# v1_4.net
KiCad netlist of a schematic drawn in EAGLE
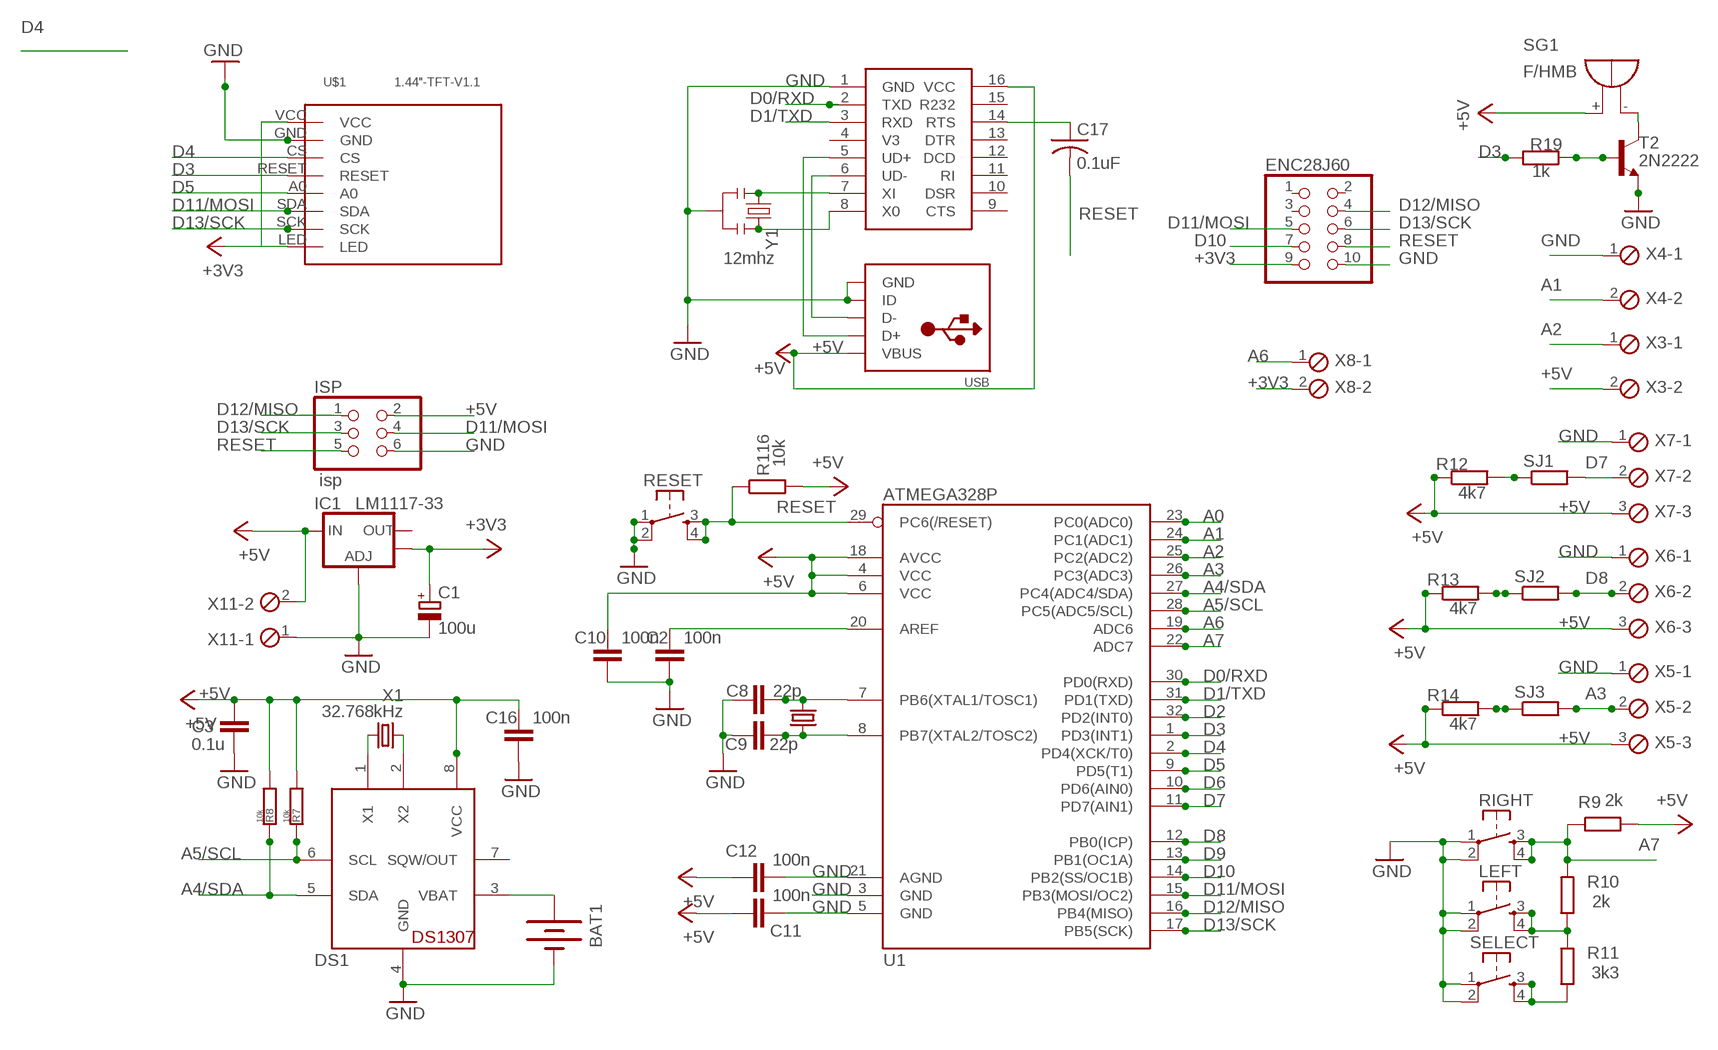
[diagram p0: schematic, sheet 1]

(export (version "E")
  (design (tool "Eeschema 10.0.6"))
  (components
    (comp (ref "BAT1")
      (value "BATTERY20PTH")
      (footprint "eagle-import:BATTCOM_20MM_PTH")
      (libsource (lib "eagle-import") (part "BATTERY20PTH"))
    )
    (comp (ref "C1")
      (value "100u")
      (footprint "eagle-import:E2-5")
      (libsource (lib "eagle-import") (part "CPOL-EUE2-5"))
    )
    (comp (ref "C2")
      (value "100n")
      (footprint "eagle-import:C0805")
      (libsource (lib "eagle-import") (part "resistor_C-EUC0805"))
    )
    (comp (ref "C3")
      (value "0.1u")
      (footprint "eagle-import:C0805")
      (libsource (lib "eagle-import") (part "C-EUC0805"))
    )
    (comp (ref "C8")
      (value "22p")
      (footprint "eagle-import:C0805")
      (libsource (lib "eagle-import") (part "resistor_C-EUC0805"))
    )
    (comp (ref "C9")
      (value "22p")
      (footprint "eagle-import:C0805")
      (libsource (lib "eagle-import") (part "resistor_C-EUC0805"))
    )
    (comp (ref "C10")
      (value "100n")
      (footprint "eagle-import:C0805")
      (libsource (lib "eagle-import") (part "resistor_C-EUC0805"))
    )
    (comp (ref "C11")
      (value "100n")
      (footprint "eagle-import:C0805")
      (libsource (lib "eagle-import") (part "resistor_C-EUC0805"))
    )
    (comp (ref "C12")
      (value "100n")
      (footprint "eagle-import:C0805")
      (libsource (lib "eagle-import") (part "resistor_C-EUC0805"))
    )
    (comp (ref "C16")
      (value "100n")
      (footprint "eagle-import:C0805")
      (libsource (lib "eagle-import") (part "resistor_C-EUC0805"))
    )
    (comp (ref "C17")
      (value "0.1uF")
      (footprint "eagle-import:C0805K")
      (libsource (lib "eagle-import") (part "C-USC0805K"))
    )
    (comp (ref "DS1")
      (value "DS1307")
      (footprint "eagle-import:SO08")
      (libsource (lib "eagle-import") (part "DS1307SOIC"))
    )
    (comp (ref "ENC28J60")
      (value "PINHD-2X5")
      (footprint "eagle-import:2X05")
      (libsource (lib "eagle-import") (part "PINHD-2X5"))
    )
    (comp (ref "IC1")
      (value "LM1117-33")
      (footprint "eagle-import:SOT223")
      (libsource (lib "eagle-import") (part "V_REG_LM1117SOT223"))
    )
    (comp (ref "ISP")
      (value "isp")
      (footprint "eagle-import:2X03")
      (libsource (lib "eagle-import") (part "PINHD-2X3"))
    )
    (comp (ref "LEFT")
      (value "TAC_SWITCHPTH")
      (footprint "eagle-import:TACTILE-PTH")
      (libsource (lib "eagle-import") (part "TAC_SWITCHPTH"))
    )
    (comp (ref "R7")
      (value "10k")
      (footprint "eagle-import:R0805")
      (libsource (lib "eagle-import") (part "R-EU_R0805"))
    )
    (comp (ref "R8")
      (value "10k")
      (footprint "eagle-import:R0805")
      (libsource (lib "eagle-import") (part "R-EU_R0805"))
    )
    (comp (ref "R9")
      (value "2k")
      (footprint "eagle-import:R0805")
      (libsource (lib "eagle-import") (part "R-EU_R0805"))
    )
    (comp (ref "R10")
      (value "2k")
      (footprint "eagle-import:R0805")
      (libsource (lib "eagle-import") (part "R-EU_R0805"))
    )
    (comp (ref "R11")
      (value "3k3")
      (footprint "eagle-import:R0805")
      (libsource (lib "eagle-import") (part "R-EU_R0805"))
    )
    (comp (ref "R12")
      (value "4k7")
      (footprint "eagle-import:R0805")
      (libsource (lib "eagle-import") (part "R-EU_R0805"))
    )
    (comp (ref "R13")
      (value "4k7")
      (footprint "eagle-import:R0805")
      (libsource (lib "eagle-import") (part "R-EU_R0805"))
    )
    (comp (ref "R14")
      (value "4k7")
      (footprint "eagle-import:R0805")
      (libsource (lib "eagle-import") (part "R-EU_R0805"))
    )
    (comp (ref "R19")
      (value "1k")
      (footprint "eagle-import:R0805")
      (libsource (lib "eagle-import") (part "R-EU_R0805"))
    )
    (comp (ref "R116")
      (value "10k")
      (footprint "eagle-import:R0805")
      (libsource (lib "eagle-import") (part "R-EU_R0805"))
    )
    (comp (ref "RESET")
      (value "TAC_SWITCHPTH")
      (footprint "eagle-import:TACTILE-PTH")
      (libsource (lib "eagle-import") (part "TAC_SWITCHPTH"))
    )
    (comp (ref "RIGHT")
      (value "TAC_SWITCHPTH")
      (footprint "eagle-import:TACTILE-PTH")
      (libsource (lib "eagle-import") (part "TAC_SWITCHPTH"))
    )
    (comp (ref "SELECT")
      (value "TAC_SWITCHPTH")
      (footprint "eagle-import:TACTILE-PTH")
      (libsource (lib "eagle-import") (part "TAC_SWITCHPTH"))
    )
    (comp (ref "SG1")
      (value "F/HMB")
      (footprint "eagle-import:F_HMB")
      (libsource (lib "eagle-import") (part "F/HMB"))
    )
    (comp (ref "SJ1")
      (value "R-EU_R0402")
      (footprint "eagle-import:R0402")
      (libsource (lib "eagle-import") (part "R-EU_R0402"))
    )
    (comp (ref "SJ2")
      (value "R-EU_R0402")
      (footprint "eagle-import:R0402")
      (libsource (lib "eagle-import") (part "R-EU_R0402"))
    )
    (comp (ref "SJ3")
      (value "R-EU_R0402")
      (footprint "eagle-import:R0402")
      (libsource (lib "eagle-import") (part "R-EU_R0402"))
    )
    (comp (ref "T2")
      (value "2N2222")
      (footprint "eagle-import:TO92-EBC-OVAL")
      (libsource (lib "eagle-import") (part "2N2222"))
    )
    (comp (ref "U$1")
      (value "1.44\"-TFT-V1.1")
      (footprint "eagle-import:1.44-TFT-V1.1")
      (libsource (lib "eagle-import") (part "1.44{dblquote}-TFT-V1.1"))
    )
    (comp (ref "U$2")
      (value "CH340G")
      (footprint "eagle-import:SO016")
      (libsource (lib "eagle-import") (part "CH340G"))
    )
    (comp (ref "U1")
      (value "ATMEGA328P")
      (footprint "eagle-import:TQFP32-08")
      (libsource (lib "eagle-import") (part "ATMEGA328_SMT"))
    )
    (comp (ref "USB")
      (value "USBMOLEX")
      (footprint "eagle-import:USB-MINIB-THM-MOLEX")
      (libsource (lib "eagle-import") (part "USBMOLEX"))
    )
    (comp (ref "X1")
      (value "32.768kHz")
      (footprint "eagle-import:TC26H")
      (libsource (lib "eagle-import") (part "crystal_CRYSTALTC26H"))
    )
    (comp (ref "X2")
      (value "16MHz")
      (footprint "eagle-import:HC49US")
      (libsource (lib "eagle-import") (part "CRYSTALHC49US"))
    )
    (comp (ref "X3")
      (value "MPT2")
      (footprint "eagle-import:2POL254")
      (libsource (lib "eagle-import") (part "MPT2"))
    )
    (comp (ref "X4")
      (value "MPT2")
      (footprint "eagle-import:2POL254")
      (libsource (lib "eagle-import") (part "MPT2"))
    )
    (comp (ref "X5")
      (value "MPT3")
      (footprint "eagle-import:3POL254")
      (libsource (lib "eagle-import") (part "MPT3"))
    )
    (comp (ref "X6")
      (value "MPT3")
      (footprint "eagle-import:3POL254")
      (libsource (lib "eagle-import") (part "MPT3"))
    )
    (comp (ref "X7")
      (value "MPT3")
      (footprint "eagle-import:3POL254")
      (libsource (lib "eagle-import") (part "MPT3"))
    )
    (comp (ref "X8")
      (value "MPT2")
      (footprint "eagle-import:2POL254")
      (libsource (lib "eagle-import") (part "MPT2"))
    )
    (comp (ref "X11")
      (value "MPT2")
      (footprint "eagle-import:2POL254")
      (fields (field (name "OC_FARNELL") "unknown") (field (name "OC_NEWARK") "unknown"))
      (libsource (lib "eagle-import") (part "MPT2"))
    )
    (comp (ref "Y1")
      (value "12mhz")
      (footprint "eagle-import:RESONATOR-PTH")
      (libsource (lib "eagle-import") (part "RESONATORPTH"))
    )
  )
  (nets
    (net (code "1") (name "+3V3") (class "Default")
      (node (ref "C1") (pin "+") (pinfunction "+_+") (pintype "passive"))
      (node (ref "ENC28J60") (pin "9") (pinfunction "9_9") (pintype "passive"))
      (node (ref "IC1") (pin "4") (pinfunction "OUT_4") (pintype "bidirectional"))
      (node (ref "U$1") (pin "LED") (pinfunction "LED_LED") (pintype "bidirectional"))
      (node (ref "U$1") (pin "VCC") (pinfunction "VCC_VCC") (pintype "bidirectional"))
      (node (ref "X8") (pin "2") (pinfunction "1_2") (pintype "passive"))
    )
    (net (code "2") (name "+5V") (class "Default")
      (node (ref "C10") (pin "1") (pinfunction "1_1") (pintype "passive"))
      (node (ref "C11") (pin "2") (pinfunction "2_2") (pintype "passive"))
      (node (ref "C12") (pin "2") (pinfunction "2_2") (pintype "passive"))
      (node (ref "C16") (pin "1") (pinfunction "1_1") (pintype "passive"))
      (node (ref "C3") (pin "1") (pinfunction "1_1") (pintype "passive"))
      (node (ref "DS1") (pin "8") (pinfunction "VCC_8") (pintype "power_in"))
      (node (ref "IC1") (pin "3") (pinfunction "IN_3") (pintype "input"))
      (node (ref "ISP") (pin "2") (pinfunction "2_2") (pintype "passive"))
      (node (ref "R116") (pin "2") (pinfunction "2_2") (pintype "passive"))
      (node (ref "R12") (pin "1") (pinfunction "1_1") (pintype "passive"))
      (node (ref "R13") (pin "1") (pinfunction "1_1") (pintype "passive"))
      (node (ref "R14") (pin "1") (pinfunction "1_1") (pintype "passive"))
      (node (ref "R7") (pin "2") (pinfunction "2_2") (pintype "passive"))
      (node (ref "R8") (pin "2") (pinfunction "2_2") (pintype "passive"))
      (node (ref "R9") (pin "2") (pinfunction "2_2") (pintype "passive"))
      (node (ref "SG1") (pin "+") (pinfunction "+_+") (pintype "passive"))
      (node (ref "U$2") (pin "16") (pinfunction "VCC_16") (pintype "bidirectional"))
      (node (ref "U1") (pin "18") (pinfunction "AVCC_18") (pintype "bidirectional"))
      (node (ref "U1") (pin "4") (pinfunction "VCC_4") (pintype "bidirectional"))
      (node (ref "U1") (pin "6") (pinfunction "VCC_6") (pintype "bidirectional"))
      (node (ref "USB") (pin "VBUS") (pinfunction "VBUS_VBUS") (pintype "power_in"))
      (node (ref "X11") (pin "2") (pinfunction "1_2") (pintype "passive"))
      (node (ref "X3") (pin "2") (pinfunction "1_2") (pintype "passive"))
      (node (ref "X5") (pin "3") (pinfunction "1_3") (pintype "passive"))
      (node (ref "X6") (pin "3") (pinfunction "1_3") (pintype "passive"))
      (node (ref "X7") (pin "3") (pinfunction "1_3") (pintype "passive"))
    )
    (net (code "3") (name "/A0") (class "Default")
      (node (ref "U1") (pin "23") (pinfunction "PC0(ADC0)_23") (pintype "bidirectional"))
    )
    (net (code "4") (name "/A1") (class "Default")
      (node (ref "U1") (pin "24") (pinfunction "PC1(ADC1)_24") (pintype "bidirectional"))
      (node (ref "X4") (pin "2") (pinfunction "1_2") (pintype "passive"))
    )
    (net (code "5") (name "/A2") (class "Default")
      (node (ref "U1") (pin "25") (pinfunction "PC2(ADC2)_25") (pintype "bidirectional"))
      (node (ref "X3") (pin "1") (pinfunction "1_1") (pintype "passive"))
    )
    (net (code "6") (name "/A3") (class "Default")
      (node (ref "SJ3") (pin "2") (pinfunction "2_2") (pintype "passive"))
      (node (ref "U1") (pin "26") (pinfunction "PC3(ADC3)_26") (pintype "bidirectional"))
      (node (ref "X5") (pin "2") (pinfunction "1_2") (pintype "passive"))
    )
    (net (code "7") (name "/A4{slash}SDA") (class "Default")
      (node (ref "DS1") (pin "5") (pinfunction "SDA_5") (pintype "bidirectional"))
      (node (ref "R8") (pin "1") (pinfunction "1_1") (pintype "passive"))
      (node (ref "U1") (pin "27") (pinfunction "PC4(ADC4/SDA)_27") (pintype "bidirectional"))
    )
    (net (code "8") (name "/A5{slash}SCL") (class "Default")
      (node (ref "DS1") (pin "6") (pinfunction "SCL_6") (pintype "bidirectional"))
      (node (ref "R7") (pin "1") (pinfunction "1_1") (pintype "passive"))
      (node (ref "U1") (pin "28") (pinfunction "PC5(ADC5/SCL)_28") (pintype "bidirectional"))
    )
    (net (code "9") (name "/A6") (class "Default")
      (node (ref "U1") (pin "19") (pinfunction "ADC6_19") (pintype "bidirectional"))
      (node (ref "X8") (pin "1") (pinfunction "1_1") (pintype "passive"))
    )
    (net (code "10") (name "/A7") (class "Default")
      (node (ref "R10") (pin "2") (pinfunction "2_2") (pintype "passive"))
      (node (ref "R9") (pin "1") (pinfunction "1_1") (pintype "passive"))
      (node (ref "RIGHT") (pin "3") (pinfunction "3_3") (pintype "passive"))
      (node (ref "RIGHT") (pin "4") (pinfunction "4_4") (pintype "passive"))
      (node (ref "U1") (pin "22") (pinfunction "ADC7_22") (pintype "bidirectional"))
    )
    (net (code "11") (name "/D0{slash}RXD") (class "Default")
      (node (ref "U$2") (pin "2") (pinfunction "TXD_2") (pintype "bidirectional"))
      (node (ref "U1") (pin "30") (pinfunction "PD0(RXD)_30") (pintype "bidirectional"))
    )
    (net (code "12") (name "/D1{slash}TXD") (class "Default")
      (node (ref "U$2") (pin "3") (pinfunction "RXD_3") (pintype "bidirectional"))
      (node (ref "U1") (pin "31") (pinfunction "PD1(TXD)_31") (pintype "bidirectional"))
    )
    (net (code "13") (name "/D2") (class "Default")
      (node (ref "U1") (pin "32") (pinfunction "PD2(INT0)_32") (pintype "bidirectional"))
    )
    (net (code "14") (name "/D3") (class "Default")
      (node (ref "R19") (pin "2") (pinfunction "2_2") (pintype "passive"))
      (node (ref "U$1") (pin "RESET") (pinfunction "RESET_RESET") (pintype "bidirectional"))
      (node (ref "U1") (pin "1") (pinfunction "PD3(INT1)_1") (pintype "bidirectional"))
    )
    (net (code "15") (name "/D4") (class "Default")
      (node (ref "U$1") (pin "CS") (pinfunction "CS_CS") (pintype "bidirectional"))
      (node (ref "U1") (pin "2") (pinfunction "PD4(XCK/T0)_2") (pintype "bidirectional"))
    )
    (net (code "16") (name "/D5") (class "Default")
      (node (ref "U$1") (pin "A0") (pinfunction "A0_A0") (pintype "bidirectional"))
      (node (ref "U1") (pin "9") (pinfunction "PD5(T1)_9") (pintype "bidirectional"))
    )
    (net (code "17") (name "/D6") (class "Default")
      (node (ref "U1") (pin "10") (pinfunction "PD6(AIN0)_10") (pintype "bidirectional"))
    )
    (net (code "18") (name "/D7") (class "Default")
      (node (ref "SJ1") (pin "2") (pinfunction "2_2") (pintype "passive"))
      (node (ref "U1") (pin "11") (pinfunction "PD7(AIN1)_11") (pintype "bidirectional"))
      (node (ref "X7") (pin "2") (pinfunction "1_2") (pintype "passive"))
    )
    (net (code "19") (name "/D8") (class "Default")
      (node (ref "SJ2") (pin "2") (pinfunction "2_2") (pintype "passive"))
      (node (ref "U1") (pin "12") (pinfunction "PB0(ICP)_12") (pintype "bidirectional"))
      (node (ref "X6") (pin "2") (pinfunction "1_2") (pintype "passive"))
    )
    (net (code "20") (name "/D9") (class "Default")
      (node (ref "U1") (pin "13") (pinfunction "PB1(OC1A)_13") (pintype "bidirectional"))
    )
    (net (code "21") (name "/D10") (class "Default")
      (node (ref "ENC28J60") (pin "7") (pinfunction "7_7") (pintype "passive"))
      (node (ref "U1") (pin "14") (pinfunction "PB2(SS/OC1B)_14") (pintype "bidirectional"))
    )
    (net (code "22") (name "/D11{slash}MOSI") (class "Default")
      (node (ref "ENC28J60") (pin "5") (pinfunction "5_5") (pintype "passive"))
      (node (ref "ISP") (pin "4") (pinfunction "4_4") (pintype "passive"))
      (node (ref "U$1") (pin "SDA") (pinfunction "SDA_SDA") (pintype "bidirectional"))
      (node (ref "U1") (pin "15") (pinfunction "PB3(MOSI/OC2)_15") (pintype "bidirectional"))
    )
    (net (code "23") (name "/D12{slash}MISO") (class "Default")
      (node (ref "ENC28J60") (pin "4") (pinfunction "4_4") (pintype "passive"))
      (node (ref "ISP") (pin "1") (pinfunction "1_1") (pintype "passive"))
      (node (ref "U1") (pin "16") (pinfunction "PB4(MISO)_16") (pintype "bidirectional"))
    )
    (net (code "24") (name "/D13{slash}SCK") (class "Default")
      (node (ref "ENC28J60") (pin "6") (pinfunction "6_6") (pintype "passive"))
      (node (ref "ISP") (pin "3") (pinfunction "3_3") (pintype "passive"))
      (node (ref "U$1") (pin "SCK") (pinfunction "SCK_SCK") (pintype "bidirectional"))
      (node (ref "U1") (pin "17") (pinfunction "PB5(SCK)_17") (pintype "bidirectional"))
    )
    (net (code "25") (name "/RESET") (class "Default")
      (node (ref "C17") (pin "2") (pinfunction "2_2") (pintype "passive"))
      (node (ref "ENC28J60") (pin "8") (pinfunction "8_8") (pintype "passive"))
      (node (ref "ISP") (pin "5") (pinfunction "5_5") (pintype "passive"))
      (node (ref "R116") (pin "1") (pinfunction "1_1") (pintype "passive"))
      (node (ref "RESET") (pin "3") (pinfunction "3_3") (pintype "passive"))
      (node (ref "RESET") (pin "4") (pinfunction "4_4") (pintype "passive"))
      (node (ref "U1") (pin "29") (pinfunction "PC6(/RESET)_29") (pintype "bidirectional"))
    )
    (net (code "26") (name "GND") (class "Default")
      (node (ref "BAT1") (pin "2") (pinfunction "-_2") (pintype "power_in"))
      (node (ref "C1") (pin "-") (pinfunction "-_-") (pintype "passive"))
      (node (ref "C10") (pin "2") (pinfunction "2_2") (pintype "passive"))
      (node (ref "C11") (pin "1") (pinfunction "1_1") (pintype "passive"))
      (node (ref "C12") (pin "1") (pinfunction "1_1") (pintype "passive"))
      (node (ref "C16") (pin "2") (pinfunction "2_2") (pintype "passive"))
      (node (ref "C2") (pin "2") (pinfunction "2_2") (pintype "passive"))
      (node (ref "C3") (pin "2") (pinfunction "2_2") (pintype "passive"))
      (node (ref "C8") (pin "1") (pinfunction "1_1") (pintype "passive"))
      (node (ref "C9") (pin "1") (pinfunction "1_1") (pintype "passive"))
      (node (ref "DS1") (pin "4") (pinfunction "GND_4") (pintype "power_in"))
      (node (ref "ENC28J60") (pin "10") (pinfunction "10_10") (pintype "passive"))
      (node (ref "IC1") (pin "1") (pinfunction "ADJ_1") (pintype "input"))
      (node (ref "ISP") (pin "6") (pinfunction "6_6") (pintype "passive"))
      (node (ref "LEFT") (pin "1") (pinfunction "1_1") (pintype "passive"))
      (node (ref "LEFT") (pin "2") (pinfunction "2_2") (pintype "passive"))
      (node (ref "RESET") (pin "1") (pinfunction "1_1") (pintype "passive"))
      (node (ref "RESET") (pin "2") (pinfunction "2_2") (pintype "passive"))
      (node (ref "RIGHT") (pin "1") (pinfunction "1_1") (pintype "passive"))
      (node (ref "RIGHT") (pin "2") (pinfunction "2_2") (pintype "passive"))
      (node (ref "SELECT") (pin "1") (pinfunction "1_1") (pintype "passive"))
      (node (ref "SELECT") (pin "2") (pinfunction "2_2") (pintype "passive"))
      (node (ref "T2") (pin "E") (pinfunction "E_E") (pintype "passive"))
      (node (ref "U$1") (pin "GND") (pinfunction "GND_GND") (pintype "bidirectional"))
      (node (ref "U$2") (pin "1") (pinfunction "GND_1") (pintype "bidirectional"))
      (node (ref "U1") (pin "21") (pinfunction "AGND_21") (pintype "bidirectional"))
      (node (ref "U1") (pin "3") (pinfunction "GND_3") (pintype "bidirectional"))
      (node (ref "U1") (pin "5") (pinfunction "GND_5") (pintype "bidirectional"))
      (node (ref "USB") (pin "GND") (pinfunction "GND_GND") (pintype "power_in"))
      (node (ref "USB") (pin "ID") (pinfunction "ID_ID") (pintype "bidirectional"))
      (node (ref "X11") (pin "1") (pinfunction "1_1") (pintype "passive"))
      (node (ref "X4") (pin "1") (pinfunction "1_1") (pintype "passive"))
      (node (ref "X5") (pin "1") (pinfunction "1_1") (pintype "passive"))
      (node (ref "X6") (pin "1") (pinfunction "1_1") (pintype "passive"))
      (node (ref "X7") (pin "1") (pinfunction "1_1") (pintype "passive"))
      (node (ref "Y1") (pin "2") (pinfunction "2_2") (pintype "passive"))
    )
    (net (code "27") (name "Net-(BAT1-+)") (class "Default")
      (node (ref "BAT1") (pin "1") (pinfunction "+_1") (pintype "power_in"))
      (node (ref "DS1") (pin "3") (pinfunction "VBAT_3") (pintype "power_in"))
    )
    (net (code "28") (name "Net-(DS1-X1)") (class "Default")
      (node (ref "DS1") (pin "1") (pinfunction "X1_1") (pintype "passive"))
      (node (ref "X1") (pin "2") (pinfunction "2_2") (pintype "passive"))
    )
    (net (code "29") (name "Net-(DS1-X2)") (class "Default")
      (node (ref "DS1") (pin "2") (pinfunction "X2_2") (pintype "passive"))
      (node (ref "X1") (pin "1") (pinfunction "1_1") (pintype "passive"))
    )
    (net (code "30") (name "Net-(LEFT-Pad3)") (class "Default")
      (node (ref "LEFT") (pin "3") (pinfunction "3_3") (pintype "passive"))
      (node (ref "LEFT") (pin "4") (pinfunction "4_4") (pintype "passive"))
      (node (ref "R10") (pin "1") (pinfunction "1_1") (pintype "passive"))
      (node (ref "R11") (pin "2") (pinfunction "2_2") (pintype "passive"))
    )
    (net (code "31") (name "Net-(R11-Pad1)") (class "Default")
      (node (ref "R11") (pin "1") (pinfunction "1_1") (pintype "passive"))
      (node (ref "SELECT") (pin "3") (pinfunction "3_3") (pintype "passive"))
      (node (ref "SELECT") (pin "4") (pinfunction "4_4") (pintype "passive"))
    )
    (net (code "32") (name "Net-(R12-Pad2)") (class "Default")
      (node (ref "R12") (pin "2") (pinfunction "2_2") (pintype "passive"))
      (node (ref "SJ1") (pin "1") (pinfunction "1_1") (pintype "passive"))
    )
    (net (code "33") (name "Net-(R13-Pad2)") (class "Default")
      (node (ref "R13") (pin "2") (pinfunction "2_2") (pintype "passive"))
      (node (ref "SJ2") (pin "1") (pinfunction "1_1") (pintype "passive"))
    )
    (net (code "34") (name "Net-(R14-Pad2)") (class "Default")
      (node (ref "R14") (pin "2") (pinfunction "2_2") (pintype "passive"))
      (node (ref "SJ3") (pin "1") (pinfunction "1_1") (pintype "passive"))
    )
    (net (code "35") (name "Net-(R19-Pad1)") (class "Default")
      (node (ref "R19") (pin "1") (pinfunction "1_1") (pintype "passive"))
      (node (ref "T2") (pin "B") (pinfunction "B_B") (pintype "passive"))
    )
    (net (code "36") (name "Net-(SG1-Pad-)") (class "Default")
      (node (ref "SG1") (pin "-") (pinfunction "-_-") (pintype "passive"))
      (node (ref "T2") (pin "C") (pinfunction "C_C") (pintype "passive"))
    )
    (net (code "37") (name "Net-(U$2-RTS)") (class "Default")
      (node (ref "C17") (pin "1") (pinfunction "1_1") (pintype "passive"))
      (node (ref "U$2") (pin "14") (pinfunction "RTS_14") (pintype "bidirectional"))
    )
    (net (code "38") (name "Net-(U$2-UD+)") (class "Default")
      (node (ref "U$2") (pin "5") (pinfunction "UD+_5") (pintype "bidirectional"))
      (node (ref "USB") (pin "D+") (pinfunction "D+_D+") (pintype "bidirectional"))
    )
    (net (code "39") (name "Net-(U$2-UD-)") (class "Default")
      (node (ref "U$2") (pin "6") (pinfunction "UD-_6") (pintype "bidirectional"))
      (node (ref "USB") (pin "D-") (pinfunction "D-_D-") (pintype "bidirectional"))
    )
    (net (code "40") (name "Net-(U$2-X0)") (class "Default")
      (node (ref "U$2") (pin "8") (pinfunction "X0_8") (pintype "bidirectional"))
      (node (ref "Y1") (pin "3") (pinfunction "3_3") (pintype "passive"))
    )
    (net (code "41") (name "Net-(U$2-XI)") (class "Default")
      (node (ref "U$2") (pin "7") (pinfunction "XI_7") (pintype "bidirectional"))
      (node (ref "Y1") (pin "1") (pinfunction "1_1") (pintype "passive"))
    )
    (net (code "42") (name "Net-(U1-AREF)") (class "Default")
      (node (ref "C2") (pin "1") (pinfunction "1_1") (pintype "passive"))
      (node (ref "U1") (pin "20") (pinfunction "AREF_20") (pintype "bidirectional"))
    )
    (net (code "43") (name "Net-(U1-PB6(XTAL1{slash}TOSC1))") (class "Default")
      (node (ref "C8") (pin "2") (pinfunction "2_2") (pintype "passive"))
      (node (ref "U1") (pin "7") (pinfunction "PB6(XTAL1/TOSC1)_7") (pintype "bidirectional"))
      (node (ref "X2") (pin "2") (pinfunction "2_2") (pintype "passive"))
    )
    (net (code "44") (name "Net-(U1-PB7(XTAL2{slash}TOSC2))") (class "Default")
      (node (ref "C9") (pin "2") (pinfunction "2_2") (pintype "passive"))
      (node (ref "U1") (pin "8") (pinfunction "PB7(XTAL2/TOSC2)_8") (pintype "bidirectional"))
      (node (ref "X2") (pin "1") (pinfunction "1_1") (pintype "passive"))
    )
    (net (code "45") (name "unconnected-(DS1-SQW{slash}OUT-Pad7)") (class "Default")
      (node (ref "DS1") (pin "7") (pinfunction "SQW/OUT_7") (pintype "bidirectional"))
    )
    (net (code "46") (name "unconnected-(ENC28J60-Pad1)") (class "Default")
      (node (ref "ENC28J60") (pin "1") (pinfunction "1_1") (pintype "passive"))
    )
    (net (code "47") (name "unconnected-(ENC28J60-Pad2)") (class "Default")
      (node (ref "ENC28J60") (pin "2") (pinfunction "2_2") (pintype "passive"))
    )
    (net (code "48") (name "unconnected-(ENC28J60-Pad3)") (class "Default")
      (node (ref "ENC28J60") (pin "3") (pinfunction "3_3") (pintype "passive"))
    )
    (net (code "49") (name "unconnected-(IC1-OUT-Pad2)") (class "Default")
      (node (ref "IC1") (pin "2") (pinfunction "OUT_2") (pintype "bidirectional"))
    )
    (net (code "50") (name "unconnected-(U$2-CTS-Pad9)") (class "Default")
      (node (ref "U$2") (pin "9") (pinfunction "CTS_9") (pintype "bidirectional"))
    )
    (net (code "51") (name "unconnected-(U$2-DCD-Pad12)") (class "Default")
      (node (ref "U$2") (pin "12") (pinfunction "DCD_12") (pintype "bidirectional"))
    )
    (net (code "52") (name "unconnected-(U$2-DSR-Pad10)") (class "Default")
      (node (ref "U$2") (pin "10") (pinfunction "DSR_10") (pintype "bidirectional"))
    )
    (net (code "53") (name "unconnected-(U$2-DTR-Pad13)") (class "Default")
      (node (ref "U$2") (pin "13") (pinfunction "DTR_13") (pintype "bidirectional"))
    )
    (net (code "54") (name "unconnected-(U$2-R232-Pad15)") (class "Default")
      (node (ref "U$2") (pin "15") (pinfunction "R232_15") (pintype "bidirectional"))
    )
    (net (code "55") (name "unconnected-(U$2-RI-Pad11)") (class "Default")
      (node (ref "U$2") (pin "11") (pinfunction "RI_11") (pintype "bidirectional"))
    )
    (net (code "56") (name "unconnected-(U$2-V3-Pad4)") (class "Default")
      (node (ref "U$2") (pin "4") (pinfunction "V3_4") (pintype "bidirectional"))
    )
  )
)
